# Analog_Inputs_12V.net
KiCad netlist of a schematic drawn in Altium Designer
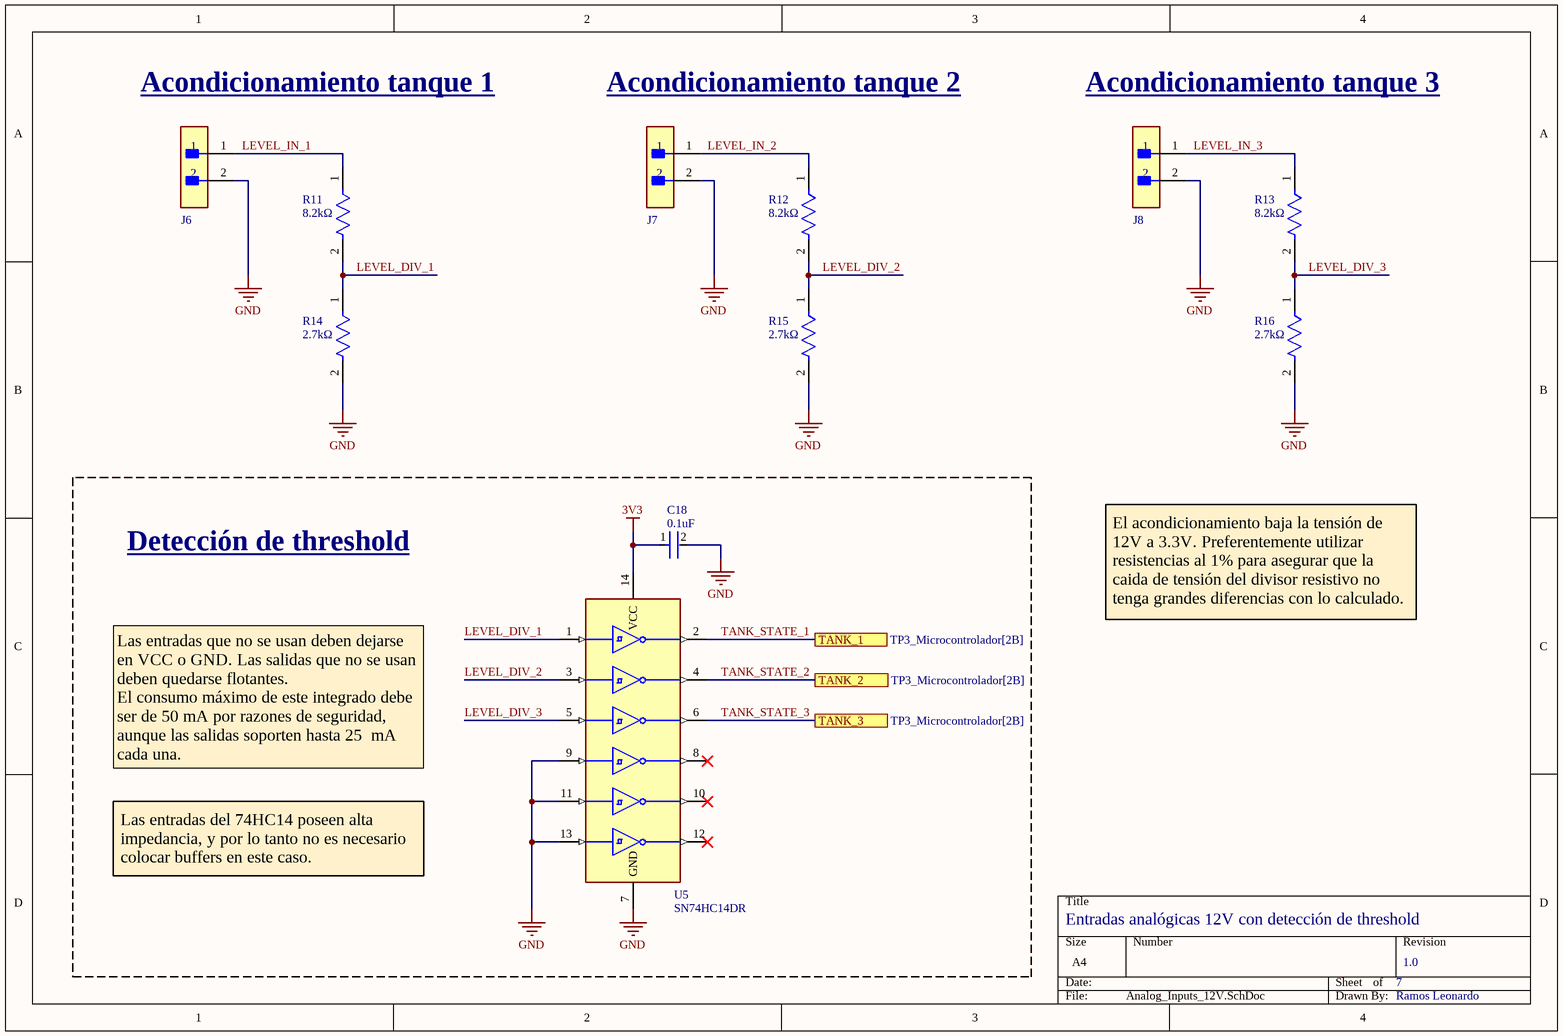
[diagram p0: Analog_Inputs_12V.SchDoc]

(export (version "E")
  (design (tool "Eeschema 10.0.6"))
  (components
    (comp (ref "C18")
      (value "0.1uF")
      (footprint "FP-CC0805-0_85-MFG")
      (description "CAP CER 0.1UF 25V X7R 0805")
      (fields (field (name "MANUFACTURER PART NUMBER") "CC0805KRX7R8BB104") (field (name "TOLERANCE") "0.1"))
      (libsource (lib "Altium Content Vault") (part "11868f565c42a9108669ba33697ecf6"))
    )
    (comp (ref "J6")
      (value "26-60-4020")
      (footprint "FP-26-60-4020-MFG")
      (description "CONN HEADER VERT 2POS 3.96MM")
      (libsource (lib "Altium Content Vault") (part "3bc925449376181038e59eaffc5286c"))
    )
    (comp (ref "J7")
      (value "26-60-4020")
      (footprint "FP-26-60-4020-MFG")
      (description "CONN HEADER VERT 2POS 3.96MM")
      (libsource (lib "Altium Content Vault") (part "3bc925449376181038e59eaffc5286c"))
    )
    (comp (ref "J8")
      (value "26-60-4020")
      (footprint "FP-26-60-4020-MFG")
      (description "CONN HEADER VERT 2POS 3.96MM")
      (libsource (lib "Altium Content Vault") (part "3bc925449376181038e59eaffc5286c"))
    )
    (comp (ref "R11")
      (value "CRCW08054K70JNEA")
      (footprint "FP-CRCW0805-e3-IPC_B")
      (description "RES Thick Film, 5%, 0.125W, 200ppm/°C, 0805")
      (fields (field (name "TOLERANCE") "5%") (field (name "RESISTANCE") "8.2kΩ"))
      (libsource (lib "Altium Content Vault") (part "1029c3af85768c4190bb7ad29bc67b5"))
    )
    (comp (ref "R12")
      (value "CRCW08054K70JNEA")
      (footprint "FP-CRCW0805-e3-IPC_B")
      (description "RES Thick Film, 5%, 0.125W, 200ppm/°C, 0805")
      (fields (field (name "TOLERANCE") "5%") (field (name "RESISTANCE") "8.2kΩ"))
      (libsource (lib "Altium Content Vault") (part "1029c3af85768c4190bb7ad29bc67b5"))
    )
    (comp (ref "R13")
      (value "CRCW08054K70JNEA")
      (footprint "FP-CRCW0805-e3-IPC_B")
      (description "RES Thick Film, 5%, 0.125W, 200ppm/°C, 0805")
      (fields (field (name "TOLERANCE") "5%") (field (name "RESISTANCE") "8.2kΩ"))
      (libsource (lib "Altium Content Vault") (part "1029c3af85768c4190bb7ad29bc67b5"))
    )
    (comp (ref "R14")
      (value "CRCW08054K70JNEA")
      (footprint "FP-CRCW0805-e3-IPC_B")
      (description "RES Thick Film,  5%, 0.125W, 200ppm/°C, 0805")
      (fields (field (name "TOLERANCE") "5%") (field (name "RESISTANCE") "2.7kΩ"))
      (libsource (lib "Altium Content Vault") (part "1029c3af85768c4190bb7ad29bc67b5"))
    )
    (comp (ref "R15")
      (value "CRCW08054K70JNEA")
      (footprint "FP-CRCW0805-e3-IPC_B")
      (description "RES Thick Film, 5%, 0.125W, 200ppm/°C, 0805")
      (fields (field (name "TOLERANCE") "5%") (field (name "RESISTANCE") "2.7kΩ"))
      (libsource (lib "Altium Content Vault") (part "1029c3af85768c4190bb7ad29bc67b5"))
    )
    (comp (ref "R16")
      (value "CRCW08054K70JNEA")
      (footprint "FP-CRCW0805-e3-IPC_B")
      (description "RES Thick Film, 5%, 0.125W, 200ppm/°C, 0805")
      (fields (field (name "TOLERANCE") "5%") (field (name "RESISTANCE") "2.7kΩ"))
      (libsource (lib "Altium Content Vault") (part "1029c3af85768c4190bb7ad29bc67b5"))
    )
    (comp (ref "U5")
      (value "SN74HC14DR")
      (footprint "FP-D0014A-IPC_C")
      (description "IC INVERTER SCHMITT 6CH 14SOIC")
      (libsource (lib "Altium Content Vault") (part "f055c5830596d9dd18238fccf55026f"))
    )
  )
  (nets
    (net (code "1") (name "/LEVEL_DIV_1") (class "Default")
      (node (ref "R11") (pin "2") (pinfunction "2_2") (pintype "passive"))
      (node (ref "R14") (pin "1") (pinfunction "1_1") (pintype "passive"))
      (node (ref "U5") (pin "1") (pinfunction "1A_1") (pintype "input"))
    )
    (net (code "2") (name "/LEVEL_DIV_2") (class "Default")
      (node (ref "R12") (pin "2") (pinfunction "2_2") (pintype "passive"))
      (node (ref "R15") (pin "1") (pinfunction "1_1") (pintype "passive"))
      (node (ref "U5") (pin "3") (pinfunction "2A_3") (pintype "input"))
    )
    (net (code "3") (name "/LEVEL_DIV_3") (class "Default")
      (node (ref "R13") (pin "2") (pinfunction "2_2") (pintype "passive"))
      (node (ref "R16") (pin "1") (pinfunction "1_1") (pintype "passive"))
      (node (ref "U5") (pin "5") (pinfunction "3A_5") (pintype "input"))
    )
    (net (code "4") (name "/LEVEL_IN_1") (class "Default")
      (node (ref "J6") (pin "1") (pinfunction "1_1") (pintype "passive"))
      (node (ref "R11") (pin "1") (pinfunction "1_1") (pintype "passive"))
    )
    (net (code "5") (name "/LEVEL_IN_2") (class "Default")
      (node (ref "J7") (pin "1") (pinfunction "1_1") (pintype "passive"))
      (node (ref "R12") (pin "1") (pinfunction "1_1") (pintype "passive"))
    )
    (net (code "6") (name "/LEVEL_IN_3") (class "Default")
      (node (ref "J8") (pin "1") (pinfunction "1_1") (pintype "passive"))
      (node (ref "R13") (pin "1") (pinfunction "1_1") (pintype "passive"))
    )
    (net (code "7") (name "/TANK_STATE_1") (class "Default")
      (node (ref "U5") (pin "2") (pinfunction "1Y_2") (pintype "output"))
    )
    (net (code "8") (name "/TANK_STATE_2") (class "Default")
      (node (ref "U5") (pin "4") (pinfunction "2Y_4") (pintype "output"))
    )
    (net (code "9") (name "/TANK_STATE_3") (class "Default")
      (node (ref "U5") (pin "6") (pinfunction "3Y_6") (pintype "output"))
    )
    (net (code "10") (name "3V3") (class "Default")
      (node (ref "C18") (pin "1") (pinfunction "1_1") (pintype "passive"))
      (node (ref "U5") (pin "14") (pinfunction "VCC_14") (pintype "power_in"))
    )
    (net (code "11") (name "GND") (class "Default")
      (node (ref "C18") (pin "2") (pinfunction "2_2") (pintype "passive"))
      (node (ref "J6") (pin "2") (pinfunction "2_2") (pintype "passive"))
      (node (ref "J7") (pin "2") (pinfunction "2_2") (pintype "passive"))
      (node (ref "J8") (pin "2") (pinfunction "2_2") (pintype "passive"))
      (node (ref "R14") (pin "2") (pinfunction "2_2") (pintype "passive"))
      (node (ref "R15") (pin "2") (pinfunction "2_2") (pintype "passive"))
      (node (ref "R16") (pin "2") (pinfunction "2_2") (pintype "passive"))
      (node (ref "U5") (pin "11") (pinfunction "5A_11") (pintype "input"))
      (node (ref "U5") (pin "13") (pinfunction "6A_13") (pintype "input"))
      (node (ref "U5") (pin "7") (pinfunction "GND_7") (pintype "power_in"))
      (node (ref "U5") (pin "9") (pinfunction "4A_9") (pintype "input"))
    )
    (net (code "12") (name "unconnected-(U5-4Y-Pad8)") (class "Default")
      (node (ref "U5") (pin "8") (pinfunction "4Y_8") (pintype "output+no_connect"))
    )
    (net (code "13") (name "unconnected-(U5-5Y-Pad10)") (class "Default")
      (node (ref "U5") (pin "10") (pinfunction "5Y_10") (pintype "output+no_connect"))
    )
    (net (code "14") (name "unconnected-(U5-6Y-Pad12)") (class "Default")
      (node (ref "U5") (pin "12") (pinfunction "6Y_12") (pintype "output+no_connect"))
    )
  )
)
